# power.net
KiCad netlist of a schematic drawn in Altium Designer
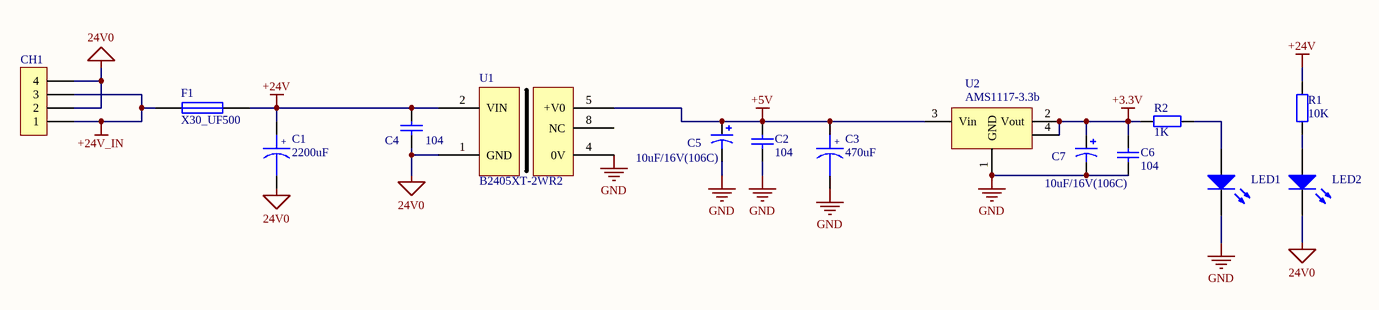
[diagram p0: power.SchDoc]

(export (version "E")
  (design (tool "Eeschema 10.0.6"))
  (components
    (comp (ref "C1")
      (value "2200uF")
      (footprint "C7.8*17")
      (fields (field (name "Comment") "C_2200uF"))
      (libsource (lib "myIntegrated_Library1") (part "C_2200uF"))
    )
    (comp (ref "C2")
      (value "104")
      (footprint "0805")
      (description "Capacitor")
      (fields (field (name "Comment") "Capb") (field (name "PUBLISHER") "Altium Limited"))
      (libsource (lib "Miscellaneous Devices") (part "Cap"))
    )
    (comp (ref "C3")
      (value "470uF")
      (footprint "C5*10")
      (fields (field (name "Comment") "C_2200uF"))
      (libsource (lib "myIntegrated_Library1") (part "C_2200uF"))
    )
    (comp (ref "C4")
      (value "104")
      (footprint "0805")
      (description "Capacitor")
      (fields (field (name "Comment") "Cap") (field (name "PUBLISHER") "Altium Limited"))
      (libsource (lib "Miscellaneous Devices") (part "Cap"))
    )
    (comp (ref "C5")
      (value "10uF/16V(106C)")
      (footprint "CAP A-3216")
      (description "Polarized Capacitor (Surface Mount)")
      (fields (field (name "Comment") "Cap Pol3b") (field (name "PUBLISHER") "Altium Limited"))
      (libsource (lib "Miscellaneous Devices") (part "Cap Pol3"))
    )
    (comp (ref "C6")
      (value "104")
      (footprint "0805")
      (description "Capacitor")
      (fields (field (name "Comment") "Capb") (field (name "PUBLISHER") "Altium Limited"))
      (libsource (lib "Miscellaneous Devices") (part "Cap"))
    )
    (comp (ref "C7")
      (value "10uF/16V(106C)")
      (footprint "CAP A-3216")
      (description "Polarized Capacitor (Surface Mount)")
      (fields (field (name "Comment") "Cap Pol3b") (field (name "PUBLISHER") "Altium Limited"))
      (libsource (lib "Miscellaneous Devices") (part "Cap Pol3"))
    )
    (comp (ref "CH1")
      (value "HEADER1X4")
      (footprint "CH3.96-4PIN")
      (libsource (lib "myIntegrated_Library1") (part "HEADER1X4"))
    )
    (comp (ref "F1")
      (value "X30_UF500")
      (footprint "X30UF600")
      (description "Fuse")
      (fields (field (name "PUBLISHER") "Altium Limited"))
      (libsource (lib "Miscellaneous Devices") (part "Fuse 1"))
    )
    (comp (ref "LED1")
      (value "~")
      (footprint "LED-0805")
      (description "Typical RED, GREEN, YELLOW, AMBER GaAs LED")
      (fields (field (name "PUBLISHER") "Altium Limited"))
      (libsource (lib "Miscellaneous Devices") (part "LED2"))
    )
    (comp (ref "LED2")
      (value "~")
      (footprint "LED-0805")
      (description "Typical RED, GREEN, YELLOW, AMBER GaAs LED")
      (fields (field (name "PUBLISHER") "Altium Limited"))
      (libsource (lib "Miscellaneous Devices") (part "LED2"))
    )
    (comp (ref "R1")
      (value "10K")
      (footprint "0805")
      (description "Resistor")
      (fields (field (name "Comment") "Res2") (field (name "PUBLISHER") "Altium Limited"))
      (libsource (lib "Miscellaneous Devices") (part "Res2"))
    )
    (comp (ref "R2")
      (value "1K")
      (footprint "0805")
      (description "Resistor")
      (fields (field (name "Comment") "Res2") (field (name "PUBLISHER") "Altium Limited"))
      (libsource (lib "") (part "Res2_1"))
    )
    (comp (ref "U1")
      (value "B2405XT-2WR2")
      (footprint "B2405XT-2WR2")
      (libsource (lib "myIntegrated_Library1") (part "B2405XT-2WR2"))
    )
    (comp (ref "U2")
      (value "AMS1117-3.3b")
      (footprint "SOT223")
      (libsource (lib "货架电子标签元件库") (part "AMS1117-5"))
    )
  )
  (nets
    (net (code "1") (name "+3.3V") (class "Default")
      (node (ref "C6") (pin "2") (pinfunction "2_2") (pintype "passive"))
      (node (ref "C7") (pin "1") (pinfunction "1_1") (pintype "passive"))
      (node (ref "R2") (pin "2") (pinfunction "2_2") (pintype "passive"))
      (node (ref "U2") (pin "2") (pinfunction "Vout_2") (pintype "passive"))
      (node (ref "U2") (pin "4") (pintype "passive"))
    )
    (net (code "2") (name "+5V") (class "Default")
      (node (ref "C2") (pin "2") (pinfunction "2_2") (pintype "passive"))
      (node (ref "C3") (pin "1") (pinfunction "1_1") (pintype "passive"))
      (node (ref "C5") (pin "1") (pinfunction "1_1") (pintype "passive"))
      (node (ref "U1") (pin "5") (pinfunction "+V0_5") (pintype "passive"))
      (node (ref "U2") (pin "3") (pinfunction "Vin_3") (pintype "passive"))
    )
    (net (code "3") (name "+24V") (class "Default")
      (node (ref "C1") (pin "1") (pinfunction "1_1") (pintype "passive"))
      (node (ref "C4") (pin "2") (pinfunction "2_2") (pintype "passive"))
      (node (ref "F1") (pin "2") (pinfunction "2_2") (pintype "passive"))
      (node (ref "R1") (pin "2") (pinfunction "2_2") (pintype "passive"))
      (node (ref "U1") (pin "2") (pinfunction "VIN_2") (pintype "passive"))
    )
    (net (code "4") (name "+24V_IN") (class "Default")
      (node (ref "CH1") (pin "1") (pinfunction "1_1") (pintype "passive"))
      (node (ref "CH1") (pin "3") (pinfunction "3_3") (pintype "passive"))
      (node (ref "F1") (pin "1") (pinfunction "1_1") (pintype "passive"))
    )
    (net (code "5") (name "24V0") (class "Default")
      (node (ref "C1") (pin "2") (pinfunction "2_2") (pintype "passive"))
      (node (ref "C4") (pin "1") (pinfunction "1_1") (pintype "passive"))
      (node (ref "CH1") (pin "2") (pinfunction "2_2") (pintype "passive"))
      (node (ref "CH1") (pin "4") (pinfunction "4_4") (pintype "passive"))
      (node (ref "LED2") (pin "2") (pinfunction "K_2") (pintype "passive"))
      (node (ref "U1") (pin "1") (pinfunction "GND_1") (pintype "passive"))
    )
    (net (code "6") (name "GND") (class "Default")
      (node (ref "C2") (pin "1") (pinfunction "1_1") (pintype "passive"))
      (node (ref "C3") (pin "2") (pinfunction "2_2") (pintype "passive"))
      (node (ref "C5") (pin "2") (pinfunction "2_2") (pintype "passive"))
      (node (ref "C6") (pin "1") (pinfunction "1_1") (pintype "passive"))
      (node (ref "C7") (pin "2") (pinfunction "2_2") (pintype "passive"))
      (node (ref "LED1") (pin "2") (pinfunction "K_2") (pintype "passive"))
      (node (ref "U1") (pin "4") (pinfunction "0V_4") (pintype "passive"))
      (node (ref "U2") (pin "1") (pinfunction "GND_1") (pintype "passive"))
    )
    (net (code "7") (name "Net-(LED1-A)") (class "Default")
      (node (ref "LED1") (pin "1") (pinfunction "A_1") (pintype "passive"))
      (node (ref "R2") (pin "1") (pinfunction "1_1") (pintype "passive"))
    )
    (net (code "8") (name "Net-(LED2-A)") (class "Default")
      (node (ref "LED2") (pin "1") (pinfunction "A_1") (pintype "passive"))
      (node (ref "R1") (pin "1") (pinfunction "1_1") (pintype "passive"))
    )
    (net (code "9") (name "unconnected-(U1-NC-Pad8)") (class "Default")
      (node (ref "U1") (pin "8") (pinfunction "NC_8") (pintype "passive"))
    )
  )
)
